# differential_ac_coupled.net
KiCad netlist of a schematic drawn in EAGLE
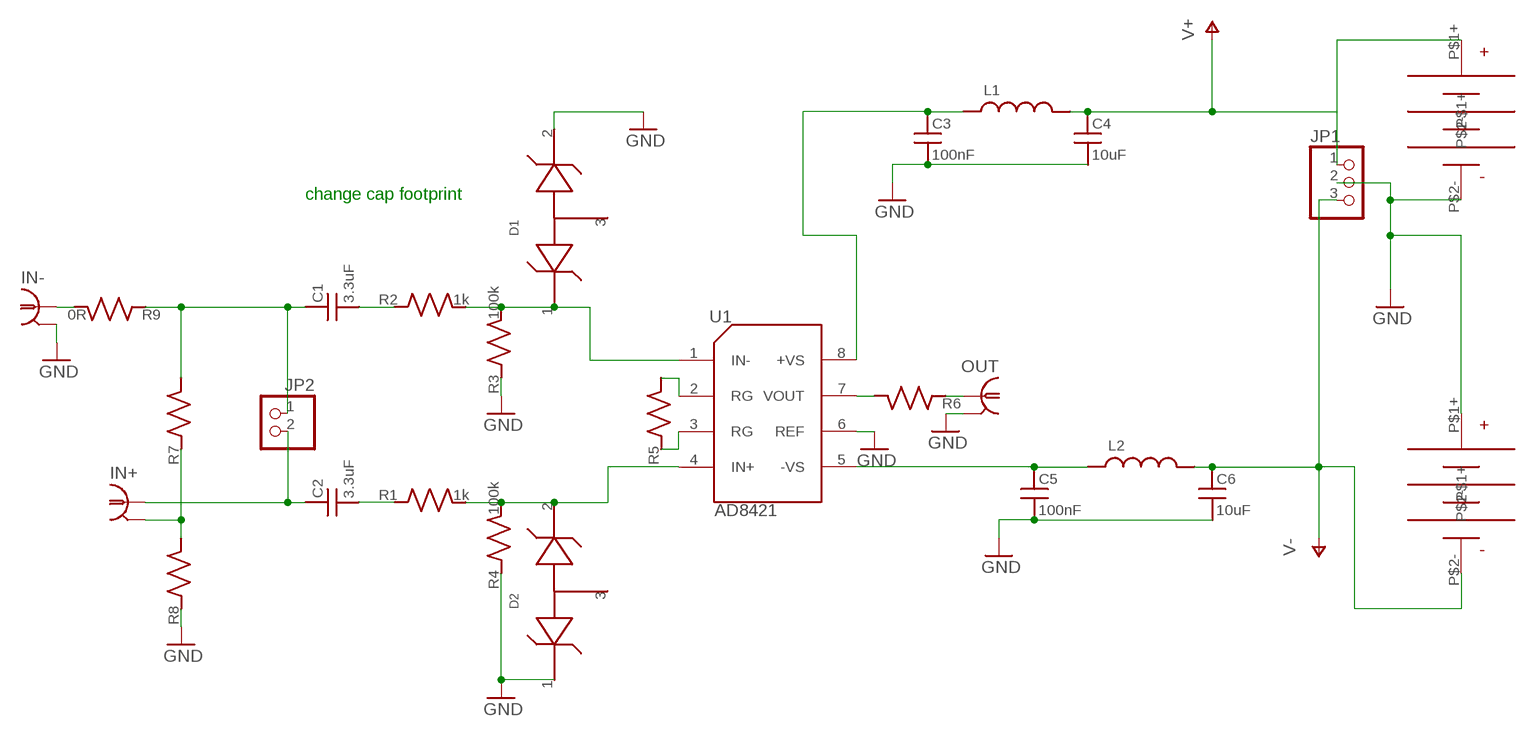
[diagram p0: schematic, sheet 1]

(export (version "E")
  (design (tool "Eeschema 10.0.6"))
  (components
    (comp (ref "C1")
      (value "3.3uF")
      (footprint "eagle-import:CKG-JLEAD")
      (libsource (lib "eagle-import") (part "C_MLCC_SMDCMLCC_JLEAD"))
    )
    (comp (ref "C2")
      (value "3.3uF")
      (footprint "eagle-import:CKG-JLEAD")
      (libsource (lib "eagle-import") (part "C_MLCC_SMDCMLCC_JLEAD"))
    )
    (comp (ref "C3")
      (value "100nF")
      (footprint "eagle-import:C_MLCC_0603")
      (libsource (lib "eagle-import") (part "C_MLCC_SMDCMLCC_0603"))
    )
    (comp (ref "C4")
      (value "10uF")
      (footprint "eagle-import:C_MLCC_0805")
      (libsource (lib "eagle-import") (part "C_MLCC_SMDCMLCC_0805"))
    )
    (comp (ref "C5")
      (value "100nF")
      (footprint "eagle-import:C_MLCC_0603")
      (libsource (lib "eagle-import") (part "C_MLCC_SMDCMLCC_0603"))
    )
    (comp (ref "C6")
      (value "10uF")
      (footprint "eagle-import:C_MLCC_0805")
      (libsource (lib "eagle-import") (part "C_MLCC_SMDCMLCC_0805"))
    )
    (comp (ref "D1")
      (value "ZENER-DUAL")
      (footprint "eagle-import:SOT-23")
      (libsource (lib "eagle-import") (part "ZENER-DUAL"))
    )
    (comp (ref "D2")
      (value "ZENER-DUAL")
      (footprint "eagle-import:SOT-23")
      (libsource (lib "eagle-import") (part "ZENER-DUAL"))
    )
    (comp (ref "IN+")
      (value "BNC-H")
      (footprint "eagle-import:BNC90")
      (libsource (lib "eagle-import") (part "BNC-H"))
    )
    (comp (ref "IN-")
      (value "BNC-H")
      (footprint "eagle-import:BNC90")
      (libsource (lib "eagle-import") (part "BNC-H"))
    )
    (comp (ref "JP1")
      (value "PINHD-1X3")
      (footprint "eagle-import:1X03")
      (libsource (lib "eagle-import") (part "PINHD-1X3"))
    )
    (comp (ref "JP2")
      (value "SCRWTRM-1X2/90_ED550")
      (footprint "eagle-import:1X02_RA_SCRWTRM_ED550")
      (libsource (lib "eagle-import") (part "SCRWTRM-1X2/90_ED550"))
    )
    (comp (ref "L1")
      (value "L_FERRITE_SMDLFERRITE_0603")
      (footprint "eagle-import:L_FERRITE_0603")
      (libsource (lib "eagle-import") (part "L_FERRITE_SMDLFERRITE_0603"))
    )
    (comp (ref "L2")
      (value "L_FERRITE_SMDLFERRITE_0603")
      (footprint "eagle-import:L_FERRITE_0603")
      (libsource (lib "eagle-import") (part "L_FERRITE_SMDLFERRITE_0603"))
    )
    (comp (ref "OUT")
      (value "BNC-H")
      (footprint "eagle-import:BNC90")
      (libsource (lib "eagle-import") (part "BNC-H"))
    )
    (comp (ref "R1")
      (value "1k")
      (footprint "eagle-import:R_1206")
      (libsource (lib "eagle-import") (part "R_SMDR1206"))
    )
    (comp (ref "R2")
      (value "1k")
      (footprint "eagle-import:R_1206")
      (libsource (lib "eagle-import") (part "R_SMDR1206"))
    )
    (comp (ref "R3")
      (value "100k")
      (footprint "eagle-import:R_1206")
      (libsource (lib "eagle-import") (part "R_SMDR1206"))
    )
    (comp (ref "R4")
      (value "100k")
      (footprint "eagle-import:R_1206")
      (libsource (lib "eagle-import") (part "R_SMDR1206"))
    )
    (comp (ref "R5")
      (value "R_SMDR0603")
      (footprint "eagle-import:R_0603")
      (libsource (lib "eagle-import") (part "R_SMDR0603"))
    )
    (comp (ref "R6")
      (value "R_SMDR0603")
      (footprint "eagle-import:R_0603")
      (libsource (lib "eagle-import") (part "R_SMDR0603"))
    )
    (comp (ref "R7")
      (value "R_SMDR1206")
      (footprint "eagle-import:R_1206")
      (libsource (lib "eagle-import") (part "R_SMDR1206"))
    )
    (comp (ref "R8")
      (value "R_SMDR1206")
      (footprint "eagle-import:R_1206")
      (libsource (lib "eagle-import") (part "R_SMDR1206"))
    )
    (comp (ref "R9")
      (value "0R")
      (footprint "eagle-import:R_1206")
      (libsource (lib "eagle-import") (part "R_SMDR1206"))
    )
    (comp (ref "U$1")
      (value "BATT-HOLDER")
      (footprint "eagle-import:BH23A-BATT-HOLDER")
      (libsource (lib "eagle-import") (part "BATT-HOLDER"))
    )
    (comp (ref "U$2")
      (value "BATT-HOLDER")
      (footprint "eagle-import:BH23A-BATT-HOLDER")
      (libsource (lib "eagle-import") (part "BATT-HOLDER"))
    )
    (comp (ref "U1")
      (value "AD8421")
      (footprint "eagle-import:SOIC-8")
      (libsource (lib "eagle-import") (part "AD8421"))
    )
  )
  (nets
    (net (code "1") (name "GND") (class "Default")
      (node (ref "C3") (pin "P$2") (pinfunction "2_P$2") (pintype "passive"))
      (node (ref "C4") (pin "P$2") (pinfunction "2_P$2") (pintype "passive"))
      (node (ref "C5") (pin "P$2") (pinfunction "2_P$2") (pintype "passive"))
      (node (ref "C6") (pin "P$2") (pinfunction "2_P$2") (pintype "passive"))
      (node (ref "D1") (pin "2") (pinfunction "P$2_2") (pintype "bidirectional"))
      (node (ref "D2") (pin "1") (pinfunction "P$1_1") (pintype "bidirectional"))
      (node (ref "IN-") (pin "2") (pinfunction "2_2") (pintype "passive"))
      (node (ref "JP1") (pin "2") (pinfunction "2_2") (pintype "passive"))
      (node (ref "OUT") (pin "2") (pinfunction "2_2") (pintype "passive"))
      (node (ref "R3") (pin "P$1") (pinfunction "1_P$1") (pintype "passive"))
      (node (ref "R4") (pin "P$1") (pinfunction "1_P$1") (pintype "passive"))
      (node (ref "R8") (pin "P$1") (pinfunction "1_P$1") (pintype "passive"))
      (node (ref "U$1") (pin "P$2-") (pinfunction "P$2-_P$2-") (pintype "bidirectional"))
      (node (ref "U$2") (pin "P$1+") (pinfunction "P$1+_P$1+") (pintype "bidirectional"))
      (node (ref "U1") (pin "6") (pinfunction "REF_6") (pintype "bidirectional"))
    )
    (net (code "2") (name "Net-(C1-1)") (class "Default")
      (node (ref "C1") (pin "P$1") (pinfunction "1_P$1") (pintype "passive"))
      (node (ref "JP2") (pin "1") (pinfunction "1_1") (pintype "passive"))
      (node (ref "R7") (pin "P$2") (pinfunction "2_P$2") (pintype "passive"))
      (node (ref "R9") (pin "P$1") (pinfunction "1_P$1") (pintype "passive"))
    )
    (net (code "3") (name "Net-(C1-2)") (class "Default")
      (node (ref "C1") (pin "P$2") (pinfunction "2_P$2") (pintype "passive"))
      (node (ref "R2") (pin "P$1") (pinfunction "1_P$1") (pintype "passive"))
    )
    (net (code "4") (name "Net-(C2-1)") (class "Default")
      (node (ref "C2") (pin "P$1") (pinfunction "1_P$1") (pintype "passive"))
      (node (ref "IN+") (pin "1") (pinfunction "1_1") (pintype "passive"))
      (node (ref "JP2") (pin "2") (pinfunction "2_2") (pintype "passive"))
    )
    (net (code "5") (name "Net-(C2-2)") (class "Default")
      (node (ref "C2") (pin "P$2") (pinfunction "2_P$2") (pintype "passive"))
      (node (ref "R1") (pin "P$1") (pinfunction "1_P$1") (pintype "passive"))
    )
    (net (code "6") (name "Net-(C3-1)") (class "Default")
      (node (ref "C3") (pin "P$1") (pinfunction "1_P$1") (pintype "passive"))
      (node (ref "L1") (pin "P$1") (pinfunction "1_P$1") (pintype "passive"))
      (node (ref "U1") (pin "8") (pinfunction "+VS_8") (pintype "bidirectional"))
    )
    (net (code "7") (name "Net-(C5-1)") (class "Default")
      (node (ref "C5") (pin "P$1") (pinfunction "1_P$1") (pintype "passive"))
      (node (ref "L2") (pin "P$1") (pinfunction "1_P$1") (pintype "passive"))
      (node (ref "U1") (pin "5") (pinfunction "-VS_5") (pintype "bidirectional"))
    )
    (net (code "8") (name "Net-(D1-P$1)") (class "Default")
      (node (ref "D1") (pin "1") (pinfunction "P$1_1") (pintype "bidirectional"))
      (node (ref "R2") (pin "P$2") (pinfunction "2_P$2") (pintype "passive"))
      (node (ref "R3") (pin "P$2") (pinfunction "2_P$2") (pintype "passive"))
      (node (ref "U1") (pin "1") (pinfunction "IN-_1") (pintype "bidirectional"))
    )
    (net (code "9") (name "Net-(D2-P$2)") (class "Default")
      (node (ref "D2") (pin "2") (pinfunction "P$2_2") (pintype "bidirectional"))
      (node (ref "R1") (pin "P$2") (pinfunction "2_P$2") (pintype "passive"))
      (node (ref "R4") (pin "P$2") (pinfunction "2_P$2") (pintype "passive"))
      (node (ref "U1") (pin "4") (pinfunction "IN+_4") (pintype "bidirectional"))
    )
    (net (code "10") (name "Net-(R5-1)") (class "Default")
      (node (ref "R5") (pin "P$1") (pinfunction "1_P$1") (pintype "passive"))
      (node (ref "U1") (pin "3") (pinfunction "RG_3") (pintype "bidirectional"))
    )
    (net (code "11") (name "Net-(R5-2)") (class "Default")
      (node (ref "R5") (pin "P$2") (pinfunction "2_P$2") (pintype "passive"))
      (node (ref "U1") (pin "2") (pinfunction "RG_2") (pintype "bidirectional"))
    )
    (net (code "12") (name "Net-(R6-1)") (class "Default")
      (node (ref "OUT") (pin "1") (pinfunction "1_1") (pintype "passive"))
      (node (ref "R6") (pin "P$1") (pinfunction "1_P$1") (pintype "passive"))
    )
    (net (code "13") (name "Net-(R6-2)") (class "Default")
      (node (ref "R6") (pin "P$2") (pinfunction "2_P$2") (pintype "passive"))
      (node (ref "U1") (pin "7") (pinfunction "VOUT_7") (pintype "bidirectional"))
    )
    (net (code "14") (name "Net-(R7-1)") (class "Default")
      (node (ref "IN+") (pin "2") (pinfunction "2_2") (pintype "passive"))
      (node (ref "R7") (pin "P$1") (pinfunction "1_P$1") (pintype "passive"))
      (node (ref "R8") (pin "P$2") (pinfunction "2_P$2") (pintype "passive"))
    )
    (net (code "15") (name "Net-(R9-2)") (class "Default")
      (node (ref "IN-") (pin "1") (pinfunction "1_1") (pintype "passive"))
      (node (ref "R9") (pin "P$2") (pinfunction "2_P$2") (pintype "passive"))
    )
    (net (code "16") (name "V+") (class "Default")
      (node (ref "C4") (pin "P$1") (pinfunction "1_P$1") (pintype "passive"))
      (node (ref "JP1") (pin "1") (pinfunction "1_1") (pintype "passive"))
      (node (ref "L1") (pin "P$2") (pinfunction "2_P$2") (pintype "passive"))
      (node (ref "U$1") (pin "P$1+") (pinfunction "P$1+_P$1+") (pintype "bidirectional"))
    )
    (net (code "17") (name "V-") (class "Default")
      (node (ref "C6") (pin "P$1") (pinfunction "1_P$1") (pintype "passive"))
      (node (ref "JP1") (pin "3") (pinfunction "3_3") (pintype "passive"))
      (node (ref "L2") (pin "P$2") (pinfunction "2_P$2") (pintype "passive"))
      (node (ref "U$2") (pin "P$2-") (pinfunction "P$2-_P$2-") (pintype "bidirectional"))
    )
    (net (code "18") (name "unconnected-(D1-P$3-Pad3)") (class "Default")
      (node (ref "D1") (pin "3") (pinfunction "P$3_3") (pintype "bidirectional"))
    )
    (net (code "19") (name "unconnected-(D2-P$3-Pad3)") (class "Default")
      (node (ref "D2") (pin "3") (pinfunction "P$3_3") (pintype "bidirectional"))
    )
  )
)
